# fdc.net
KiCad netlist of a schematic drawn in EAGLE
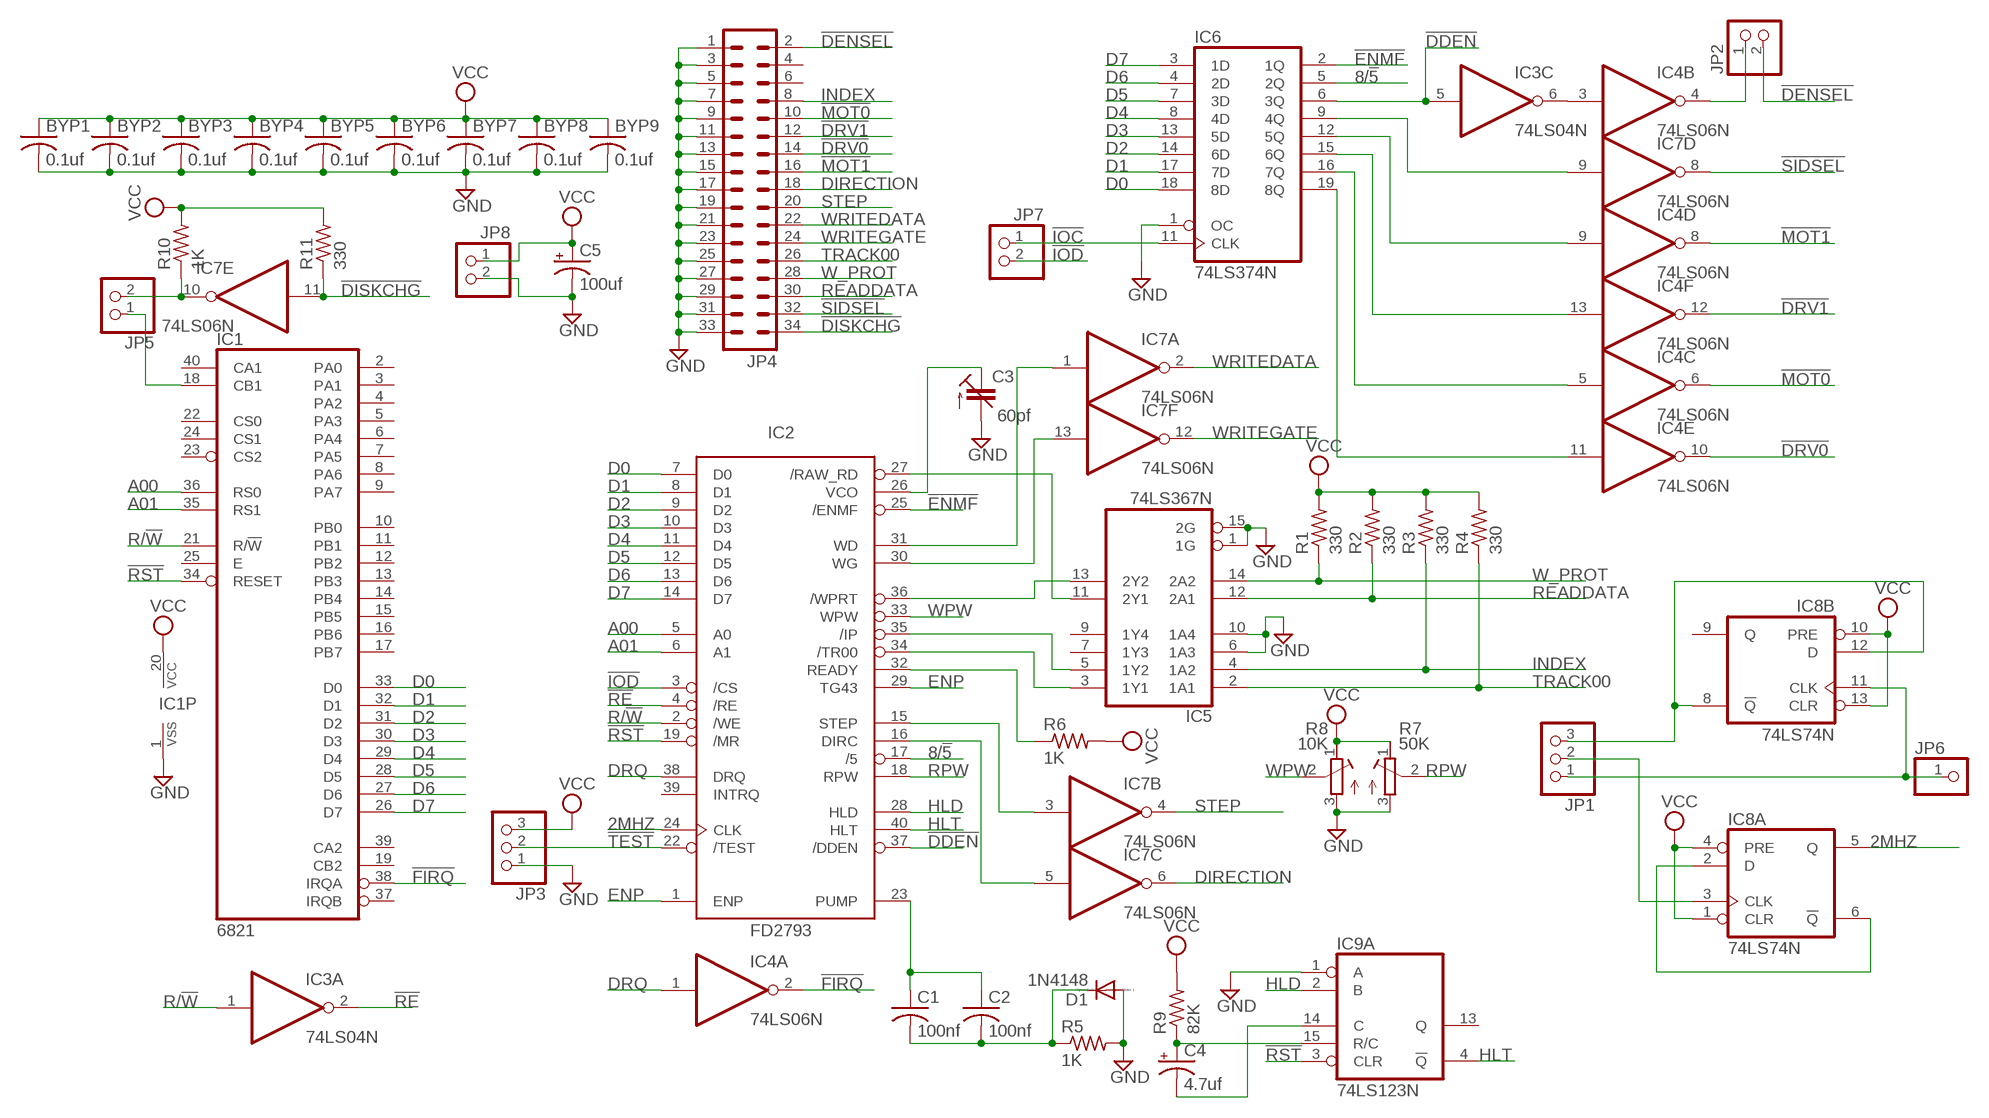
[diagram p0: schematic, sheet 1]

(export (version "E")
  (design (tool "Eeschema 10.0.6"))
  (components
    (comp (ref "BYP1")
      (value "0.1uf")
      (footprint "eagle-import:C050-025X075")
      (libsource (lib "eagle-import") (part "C-US050-025X075"))
    )
    (comp (ref "BYP2")
      (value "0.1uf")
      (footprint "eagle-import:C050-025X075")
      (libsource (lib "eagle-import") (part "C-US050-025X075"))
    )
    (comp (ref "BYP3")
      (value "0.1uf")
      (footprint "eagle-import:C050-025X075")
      (libsource (lib "eagle-import") (part "C-US050-025X075"))
    )
    (comp (ref "BYP4")
      (value "0.1uf")
      (footprint "eagle-import:C050-025X075")
      (libsource (lib "eagle-import") (part "C-US050-025X075"))
    )
    (comp (ref "BYP5")
      (value "0.1uf")
      (footprint "eagle-import:C050-025X075")
      (libsource (lib "eagle-import") (part "C-US050-025X075"))
    )
    (comp (ref "BYP6")
      (value "0.1uf")
      (footprint "eagle-import:C050-025X075")
      (libsource (lib "eagle-import") (part "C-US050-025X075"))
    )
    (comp (ref "BYP7")
      (value "0.1uf")
      (footprint "eagle-import:C050-025X075")
      (libsource (lib "eagle-import") (part "C-US050-025X075"))
    )
    (comp (ref "BYP8")
      (value "0.1uf")
      (footprint "eagle-import:C050-025X075")
      (libsource (lib "eagle-import") (part "C-US050-025X075"))
    )
    (comp (ref "BYP9")
      (value "0.1uf")
      (footprint "eagle-import:C050-025X075")
      (libsource (lib "eagle-import") (part "C-US050-025X075"))
    )
    (comp (ref "C1")
      (value "100nf")
      (footprint "eagle-import:C050-025X075")
      (libsource (lib "eagle-import") (part "C-US050-025X075"))
    )
    (comp (ref "C2")
      (value "100nf")
      (footprint "eagle-import:C050-025X075")
      (libsource (lib "eagle-import") (part "C-US050-025X075"))
    )
    (comp (ref "C3")
      (value "60pf")
      (footprint "eagle-import:CTRIM808-BC")
      (libsource (lib "eagle-import") (part "C-TRIMM808"))
    )
    (comp (ref "C4")
      (value "4.7uf")
      (footprint "eagle-import:E15-5")
      (libsource (lib "eagle-import") (part "CPOL-USE15-5AXIAL"))
    )
    (comp (ref "C5")
      (value "100uf")
      (footprint "eagle-import:E15-5")
      (libsource (lib "eagle-import") (part "CPOL-USE15-5AXIAL"))
    )
    (comp (ref "D1")
      (value "1N4148")
      (footprint "eagle-import:DO35-10")
      (libsource (lib "eagle-import") (part "1N4148DO35-10"))
    )
    (comp (ref "IC1")
      (value "6821")
      (footprint "eagle-import:DIL40")
      (fields (field (name "MF") "NTE ELECTRONICS") (field (name "MPN") "NTE6821"))
      (libsource (lib "eagle-import") (part "6821"))
    )
    (comp (ref "IC2")
      (value "FD2793")
      (footprint "eagle-import:DIL40")
      (libsource (lib "eagle-import") (part "FD2793"))
    )
    (comp (ref "IC3")
      (value "74LS04N")
      (footprint "eagle-import:DIL14")
      (libsource (lib "eagle-import") (part "7404NLS"))
    )
    (comp (ref "IC4")
      (value "74LS06N")
      (footprint "eagle-import:DIL14")
      (libsource (lib "eagle-import") (part "7406NLS"))
    )
    (comp (ref "IC5")
      (value "74LS367N")
      (footprint "eagle-import:DIL16")
      (libsource (lib "eagle-import") (part "74367N"))
    )
    (comp (ref "IC6")
      (value "74LS374N")
      (footprint "eagle-import:DIL20")
      (libsource (lib "eagle-import") (part "74374NLS"))
    )
    (comp (ref "IC7")
      (value "74LS06N")
      (footprint "eagle-import:DIL14")
      (libsource (lib "eagle-import") (part "7406NLS"))
    )
    (comp (ref "IC8")
      (value "74LS74N")
      (footprint "eagle-import:DIL14")
      (libsource (lib "eagle-import") (part "7474NLS"))
    )
    (comp (ref "IC9")
      (value "74LS123N")
      (footprint "eagle-import:DIL16")
      (libsource (lib "eagle-import") (part "74123NLS"))
    )
    (comp (ref "JP1")
      (value "PINHD-1X3")
      (footprint "eagle-import:1X03")
      (libsource (lib "eagle-import") (part "PINHD-1X3"))
    )
    (comp (ref "JP2")
      (value "PINHD-1X2")
      (footprint "eagle-import:1X02")
      (libsource (lib "eagle-import") (part "PINHD-1X2"))
    )
    (comp (ref "JP3")
      (value "PINHD-1X3")
      (footprint "eagle-import:1X03")
      (libsource (lib "eagle-import") (part "PINHD-1X3"))
    )
    (comp (ref "JP4")
      (value "MA17-2")
      (footprint "eagle-import:MA17-2")
      (libsource (lib "eagle-import") (part "MA17-2"))
    )
    (comp (ref "JP5")
      (value "PINHD-1X2")
      (footprint "eagle-import:1X02")
      (libsource (lib "eagle-import") (part "PINHD-1X2"))
    )
    (comp (ref "JP6")
      (value "PINHD-1X1")
      (footprint "eagle-import:1X01")
      (libsource (lib "eagle-import") (part "PINHD-1X1"))
    )
    (comp (ref "JP7")
      (value "PINHD-1X2")
      (footprint "eagle-import:1X02")
      (libsource (lib "eagle-import") (part "PINHD-1X2"))
    )
    (comp (ref "JP8")
      (value "PINHD-1X2")
      (footprint "eagle-import:1X02")
      (libsource (lib "eagle-import") (part "PINHD-1X2"))
    )
    (comp (ref "R1")
      (value "330")
      (footprint "eagle-import:0207_10")
      (libsource (lib "eagle-import") (part "R-US_0207/10"))
    )
    (comp (ref "R2")
      (value "330")
      (footprint "eagle-import:0207_10")
      (libsource (lib "eagle-import") (part "R-US_0207/10"))
    )
    (comp (ref "R3")
      (value "330")
      (footprint "eagle-import:0207_10")
      (libsource (lib "eagle-import") (part "R-US_0207/10"))
    )
    (comp (ref "R4")
      (value "330")
      (footprint "eagle-import:0207_10")
      (libsource (lib "eagle-import") (part "R-US_0207/10"))
    )
    (comp (ref "R5")
      (value "1K")
      (footprint "eagle-import:0207_10")
      (libsource (lib "eagle-import") (part "R-US_0207/10"))
    )
    (comp (ref "R6")
      (value "1K")
      (footprint "eagle-import:0207_10")
      (libsource (lib "eagle-import") (part "R-US_0207/10"))
    )
    (comp (ref "R7")
      (value "50K")
      (footprint "eagle-import:RTRIM43P")
      (libsource (lib "eagle-import") (part "R-TRIMM43P"))
    )
    (comp (ref "R8")
      (value "10K")
      (footprint "eagle-import:RTRIM43P")
      (libsource (lib "eagle-import") (part "R-TRIMM43P"))
    )
    (comp (ref "R9")
      (value "82K")
      (footprint "eagle-import:0207_10")
      (libsource (lib "eagle-import") (part "R-US_0207/10"))
    )
    (comp (ref "R10")
      (value "1K")
      (footprint "eagle-import:0207_10")
      (libsource (lib "eagle-import") (part "R-US_0207/10"))
    )
    (comp (ref "R11")
      (value "330")
      (footprint "eagle-import:0207_10")
      (libsource (lib "eagle-import") (part "R-US_0207/10"))
    )
  )
  (nets
    (net (code "1") (name "/2MHZ") (class "Default")
      (node (ref "IC2") (pin "24") (pinfunction "CLK_24") (pintype "input"))
      (node (ref "IC8") (pin "5") (pinfunction "Q_5") (pintype "output"))
    )
    (net (code "2") (name "/8{slash}~{5}") (class "Default")
      (node (ref "IC2") (pin "17") (pinfunction "/5_17") (pintype "output"))
      (node (ref "IC6") (pin "5") (pinfunction "2Q_5") (pintype "tri_state"))
    )
    (net (code "3") (name "/A00") (class "Default")
      (node (ref "IC1") (pin "36") (pinfunction "RS0_36") (pintype "input"))
      (node (ref "IC2") (pin "5") (pinfunction "A0_5") (pintype "input"))
    )
    (net (code "4") (name "/A01") (class "Default")
      (node (ref "IC1") (pin "35") (pinfunction "RS1_35") (pintype "input"))
      (node (ref "IC2") (pin "6") (pinfunction "A1_6") (pintype "input"))
    )
    (net (code "5") (name "/D0") (class "Default")
      (node (ref "IC1") (pin "33") (pinfunction "D0_33") (pintype "bidirectional"))
      (node (ref "IC2") (pin "7") (pinfunction "D0_7") (pintype "bidirectional"))
      (node (ref "IC6") (pin "18") (pinfunction "8D_18") (pintype "input"))
    )
    (net (code "6") (name "/D1") (class "Default")
      (node (ref "IC1") (pin "32") (pinfunction "D1_32") (pintype "bidirectional"))
      (node (ref "IC2") (pin "8") (pinfunction "D1_8") (pintype "bidirectional"))
      (node (ref "IC6") (pin "17") (pinfunction "7D_17") (pintype "input"))
    )
    (net (code "7") (name "/D2") (class "Default")
      (node (ref "IC1") (pin "31") (pinfunction "D2_31") (pintype "bidirectional"))
      (node (ref "IC2") (pin "9") (pinfunction "D2_9") (pintype "bidirectional"))
      (node (ref "IC6") (pin "14") (pinfunction "6D_14") (pintype "input"))
    )
    (net (code "8") (name "/D3") (class "Default")
      (node (ref "IC1") (pin "30") (pinfunction "D3_30") (pintype "bidirectional"))
      (node (ref "IC2") (pin "10") (pinfunction "D3_10") (pintype "bidirectional"))
      (node (ref "IC6") (pin "13") (pinfunction "5D_13") (pintype "input"))
    )
    (net (code "9") (name "/D4") (class "Default")
      (node (ref "IC1") (pin "29") (pinfunction "D4_29") (pintype "bidirectional"))
      (node (ref "IC2") (pin "11") (pinfunction "D4_11") (pintype "bidirectional"))
      (node (ref "IC6") (pin "8") (pinfunction "4D_8") (pintype "input"))
    )
    (net (code "10") (name "/D5") (class "Default")
      (node (ref "IC1") (pin "28") (pinfunction "D5_28") (pintype "bidirectional"))
      (node (ref "IC2") (pin "12") (pinfunction "D5_12") (pintype "bidirectional"))
      (node (ref "IC6") (pin "7") (pinfunction "3D_7") (pintype "input"))
    )
    (net (code "11") (name "/D6") (class "Default")
      (node (ref "IC1") (pin "27") (pinfunction "D6_27") (pintype "bidirectional"))
      (node (ref "IC2") (pin "13") (pinfunction "D6_13") (pintype "bidirectional"))
      (node (ref "IC6") (pin "4") (pinfunction "2D_4") (pintype "input"))
    )
    (net (code "12") (name "/D7") (class "Default")
      (node (ref "IC1") (pin "26") (pinfunction "D7_26") (pintype "bidirectional"))
      (node (ref "IC2") (pin "14") (pinfunction "D7_14") (pintype "bidirectional"))
      (node (ref "IC6") (pin "3") (pinfunction "1D_3") (pintype "input"))
    )
    (net (code "13") (name "/DIRECTION") (class "Default")
      (node (ref "IC7") (pin "6") (pinfunction "O_6") (pintype "open_collector"))
      (node (ref "JP4") (pin "18") (pinfunction "18_18") (pintype "passive"))
    )
    (net (code "14") (name "/DRQ") (class "Default")
      (node (ref "IC2") (pin "38") (pinfunction "DRQ_38") (pintype "output"))
      (node (ref "IC4") (pin "1") (pinfunction "I_1") (pintype "input"))
    )
    (net (code "15") (name "/ENP") (class "Default")
      (node (ref "IC2") (pin "1") (pinfunction "ENP_1") (pintype "power_in"))
      (node (ref "IC2") (pin "29") (pinfunction "TG43_29") (pintype "output"))
    )
    (net (code "16") (name "/HLD") (class "Default")
      (node (ref "IC2") (pin "28") (pinfunction "HLD_28") (pintype "output"))
      (node (ref "IC9") (pin "2") (pinfunction "B_2") (pintype "input"))
    )
    (net (code "17") (name "/HLT") (class "Default")
      (node (ref "IC2") (pin "40") (pinfunction "HLT_40") (pintype "input"))
      (node (ref "IC9") (pin "4") (pinfunction "~{Q}_4") (pintype "output"))
    )
    (net (code "18") (name "/INDEX") (class "Default")
      (node (ref "IC5") (pin "4") (pinfunction "1A2_4") (pintype "input"))
      (node (ref "JP4") (pin "8") (pinfunction "8_8") (pintype "passive"))
      (node (ref "R3") (pin "1") (pinfunction "1_1") (pintype "passive"))
    )
    (net (code "19") (name "/READDATA") (class "Default")
      (node (ref "IC5") (pin "12") (pinfunction "2A1_12") (pintype "input"))
      (node (ref "JP4") (pin "30") (pinfunction "30_30") (pintype "passive"))
      (node (ref "R2") (pin "1") (pinfunction "1_1") (pintype "passive"))
    )
    (net (code "20") (name "/RPW") (class "Default")
      (node (ref "IC2") (pin "18") (pinfunction "RPW_18") (pintype "input"))
      (node (ref "R7") (pin "2") (pinfunction "S_2") (pintype "passive"))
    )
    (net (code "21") (name "/R{slash}~{W}") (class "Default")
      (node (ref "IC1") (pin "21") (pinfunction "R/~{W}_21") (pintype "input"))
      (node (ref "IC2") (pin "2") (pinfunction "/WE_2") (pintype "input"))
      (node (ref "IC3") (pin "1") (pinfunction "I_1") (pintype "input"))
    )
    (net (code "22") (name "/STEP") (class "Default")
      (node (ref "IC7") (pin "4") (pinfunction "O_4") (pintype "open_collector"))
      (node (ref "JP4") (pin "20") (pinfunction "20_20") (pintype "passive"))
    )
    (net (code "23") (name "/TRACK00") (class "Default")
      (node (ref "IC5") (pin "2") (pinfunction "1A1_2") (pintype "input"))
      (node (ref "JP4") (pin "26") (pinfunction "26_26") (pintype "passive"))
      (node (ref "R4") (pin "1") (pinfunction "1_1") (pintype "passive"))
    )
    (net (code "24") (name "/WPW") (class "Default")
      (node (ref "IC2") (pin "33") (pinfunction "WPW_33") (pintype "input"))
      (node (ref "R8") (pin "2") (pinfunction "S_2") (pintype "passive"))
    )
    (net (code "25") (name "/WRITEDATA") (class "Default")
      (node (ref "IC7") (pin "2") (pinfunction "O_2") (pintype "open_collector"))
      (node (ref "JP4") (pin "22") (pinfunction "22_22") (pintype "passive"))
    )
    (net (code "26") (name "/WRITEGATE") (class "Default")
      (node (ref "IC7") (pin "12") (pinfunction "O_12") (pintype "open_collector"))
      (node (ref "JP4") (pin "24") (pinfunction "24_24") (pintype "passive"))
    )
    (net (code "27") (name "/W_PROT") (class "Default")
      (node (ref "IC5") (pin "14") (pinfunction "2A2_14") (pintype "input"))
      (node (ref "JP4") (pin "28") (pinfunction "28_28") (pintype "passive"))
      (node (ref "R1") (pin "1") (pinfunction "1_1") (pintype "passive"))
    )
    (net (code "28") (name "/~{DDEN}") (class "Default")
      (node (ref "IC2") (pin "37") (pinfunction "/DDEN_37") (pintype "input"))
      (node (ref "IC3") (pin "5") (pinfunction "I_5") (pintype "input"))
      (node (ref "IC6") (pin "6") (pinfunction "3Q_6") (pintype "tri_state"))
    )
    (net (code "29") (name "/~{DENSEL}") (class "Default")
      (node (ref "JP2") (pin "2") (pinfunction "2_2") (pintype "passive"))
      (node (ref "JP4") (pin "2") (pinfunction "2_2") (pintype "passive"))
    )
    (net (code "30") (name "/~{DISKCHG}") (class "Default")
      (node (ref "IC7") (pin "11") (pinfunction "I_11") (pintype "input"))
      (node (ref "JP4") (pin "34") (pinfunction "34_34") (pintype "passive"))
      (node (ref "R11") (pin "1") (pinfunction "1_1") (pintype "passive"))
    )
    (net (code "31") (name "/~{DRV0}") (class "Default")
      (node (ref "IC4") (pin "10") (pinfunction "O_10") (pintype "open_collector"))
      (node (ref "JP4") (pin "14") (pinfunction "14_14") (pintype "passive"))
    )
    (net (code "32") (name "/~{DRV1}") (class "Default")
      (node (ref "IC4") (pin "12") (pinfunction "O_12") (pintype "open_collector"))
      (node (ref "JP4") (pin "12") (pinfunction "12_12") (pintype "passive"))
    )
    (net (code "33") (name "/~{ENMF}") (class "Default")
      (node (ref "IC2") (pin "25") (pinfunction "/ENMF_25") (pintype "input"))
      (node (ref "IC6") (pin "2") (pinfunction "1Q_2") (pintype "tri_state"))
    )
    (net (code "34") (name "/~{FIRQ}") (class "Default")
      (node (ref "IC1") (pin "38") (pinfunction "IRQA_38") (pintype "open_collector"))
      (node (ref "IC4") (pin "2") (pinfunction "O_2") (pintype "open_collector"))
    )
    (net (code "35") (name "/~{IOC}") (class "Default")
      (node (ref "IC6") (pin "11") (pinfunction "CLK_11") (pintype "input"))
      (node (ref "JP7") (pin "1") (pinfunction "1_1") (pintype "passive"))
    )
    (net (code "36") (name "/~{IOD}") (class "Default")
      (node (ref "IC2") (pin "3") (pinfunction "/CS_3") (pintype "input"))
      (node (ref "JP7") (pin "2") (pinfunction "2_2") (pintype "passive"))
    )
    (net (code "37") (name "/~{MOT0}") (class "Default")
      (node (ref "IC4") (pin "6") (pinfunction "O_6") (pintype "open_collector"))
      (node (ref "JP4") (pin "10") (pinfunction "10_10") (pintype "passive"))
    )
    (net (code "38") (name "/~{MOT1}") (class "Default")
      (node (ref "IC4") (pin "8") (pinfunction "O_8") (pintype "open_collector"))
      (node (ref "JP4") (pin "16") (pinfunction "16_16") (pintype "passive"))
    )
    (net (code "39") (name "/~{RE}") (class "Default")
      (node (ref "IC2") (pin "4") (pinfunction "/RE_4") (pintype "input"))
      (node (ref "IC3") (pin "2") (pinfunction "O_2") (pintype "output"))
    )
    (net (code "40") (name "/~{RST}") (class "Default")
      (node (ref "IC1") (pin "34") (pinfunction "RESET_34") (pintype "input"))
      (node (ref "IC2") (pin "19") (pinfunction "/MR_19") (pintype "input"))
      (node (ref "IC9") (pin "3") (pinfunction "CLR_3") (pintype "input"))
    )
    (net (code "41") (name "/~{SIDSEL}") (class "Default")
      (node (ref "IC7") (pin "8") (pinfunction "O_8") (pintype "open_collector"))
      (node (ref "JP4") (pin "32") (pinfunction "32_32") (pintype "passive"))
    )
    (net (code "42") (name "/~{TEST}") (class "Default")
      (node (ref "IC2") (pin "22") (pinfunction "/TEST_22") (pintype "input"))
      (node (ref "JP3") (pin "2") (pinfunction "2_2") (pintype "passive"))
    )
    (net (code "43") (name "GND") (class "Default")
      (node (ref "BYP1") (pin "2") (pinfunction "2_2") (pintype "passive"))
      (node (ref "BYP2") (pin "2") (pinfunction "2_2") (pintype "passive"))
      (node (ref "BYP3") (pin "2") (pinfunction "2_2") (pintype "passive"))
      (node (ref "BYP4") (pin "2") (pinfunction "2_2") (pintype "passive"))
      (node (ref "BYP5") (pin "2") (pinfunction "2_2") (pintype "passive"))
      (node (ref "BYP6") (pin "2") (pinfunction "2_2") (pintype "passive"))
      (node (ref "BYP7") (pin "2") (pinfunction "2_2") (pintype "passive"))
      (node (ref "BYP8") (pin "2") (pinfunction "2_2") (pintype "passive"))
      (node (ref "BYP9") (pin "2") (pinfunction "2_2") (pintype "passive"))
      (node (ref "C3") (pin "2") (pinfunction "A_2") (pintype "passive"))
      (node (ref "C5") (pin "-") (pinfunction "-_-") (pintype "passive"))
      (node (ref "D1") (pin "A") (pinfunction "A_A") (pintype "passive"))
      (node (ref "IC1") (pin "1") (pinfunction "VSS_1") (pintype "power_in"))
      (node (ref "IC5") (pin "1") (pinfunction "1G_1") (pintype "input"))
      (node (ref "IC5") (pin "10") (pinfunction "1A4_10") (pintype "input"))
      (node (ref "IC5") (pin "15") (pinfunction "2G_15") (pintype "input"))
      (node (ref "IC5") (pin "6") (pinfunction "1A3_6") (pintype "input"))
      (node (ref "IC6") (pin "1") (pinfunction "OC_1") (pintype "input"))
      (node (ref "IC9") (pin "1") (pinfunction "A_1") (pintype "input"))
      (node (ref "JP3") (pin "1") (pinfunction "1_1") (pintype "passive"))
      (node (ref "JP4") (pin "1") (pinfunction "1_1") (pintype "passive"))
      (node (ref "JP4") (pin "11") (pinfunction "11_11") (pintype "passive"))
      (node (ref "JP4") (pin "13") (pinfunction "13_13") (pintype "passive"))
      (node (ref "JP4") (pin "15") (pinfunction "15_15") (pintype "passive"))
      (node (ref "JP4") (pin "17") (pinfunction "17_17") (pintype "passive"))
      (node (ref "JP4") (pin "19") (pinfunction "19_19") (pintype "passive"))
      (node (ref "JP4") (pin "21") (pinfunction "21_21") (pintype "passive"))
      (node (ref "JP4") (pin "23") (pinfunction "23_23") (pintype "passive"))
      (node (ref "JP4") (pin "25") (pinfunction "25_25") (pintype "passive"))
      (node (ref "JP4") (pin "27") (pinfunction "27_27") (pintype "passive"))
      (node (ref "JP4") (pin "29") (pinfunction "29_29") (pintype "passive"))
      (node (ref "JP4") (pin "3") (pinfunction "3_3") (pintype "passive"))
      (node (ref "JP4") (pin "31") (pinfunction "31_31") (pintype "passive"))
      (node (ref "JP4") (pin "33") (pinfunction "33_33") (pintype "passive"))
      (node (ref "JP4") (pin "5") (pinfunction "5_5") (pintype "passive"))
      (node (ref "JP4") (pin "7") (pinfunction "7_7") (pintype "passive"))
      (node (ref "JP4") (pin "9") (pinfunction "9_9") (pintype "passive"))
      (node (ref "JP8") (pin "2") (pinfunction "2_2") (pintype "passive"))
      (node (ref "R5") (pin "2") (pinfunction "2_2") (pintype "passive"))
      (node (ref "R7") (pin "3") (pinfunction "A_3") (pintype "passive"))
      (node (ref "R8") (pin "3") (pinfunction "A_3") (pintype "passive"))
    )
    (net (code "44") (name "Net-(C1-Pad2)") (class "Default")
      (node (ref "C1") (pin "2") (pinfunction "2_2") (pintype "passive"))
      (node (ref "C2") (pin "2") (pinfunction "2_2") (pintype "passive"))
      (node (ref "D1") (pin "C") (pinfunction "C_C") (pintype "passive"))
      (node (ref "R5") (pin "1") (pinfunction "1_1") (pintype "passive"))
    )
    (net (code "45") (name "Net-(C3-E)") (class "Default")
      (node (ref "C3") (pin "1") (pinfunction "E_1") (pintype "passive"))
      (node (ref "IC2") (pin "26") (pinfunction "VCO_26") (pintype "input"))
    )
    (net (code "46") (name "Net-(IC1A-CB1)") (class "Default")
      (node (ref "IC1") (pin "18") (pinfunction "CB1_18") (pintype "input"))
      (node (ref "JP5") (pin "1") (pinfunction "1_1") (pintype "passive"))
    )
    (net (code "47") (name "Net-(IC2A-DIRC)") (class "Default")
      (node (ref "IC2") (pin "16") (pinfunction "DIRC_16") (pintype "output"))
      (node (ref "IC7") (pin "5") (pinfunction "I_5") (pintype "input"))
    )
    (net (code "48") (name "Net-(IC2A-PUMP)") (class "Default")
      (node (ref "C1") (pin "1") (pinfunction "1_1") (pintype "passive"))
      (node (ref "C2") (pin "1") (pinfunction "1_1") (pintype "passive"))
      (node (ref "IC2") (pin "23") (pinfunction "PUMP_23") (pintype "power_in"))
    )
    (net (code "49") (name "Net-(IC2A-READY)") (class "Default")
      (node (ref "IC2") (pin "32") (pinfunction "READY_32") (pintype "input"))
      (node (ref "R6") (pin "1") (pinfunction "1_1") (pintype "passive"))
    )
    (net (code "50") (name "Net-(IC2A-STEP)") (class "Default")
      (node (ref "IC2") (pin "15") (pinfunction "STEP_15") (pintype "output"))
      (node (ref "IC7") (pin "3") (pinfunction "I_3") (pintype "input"))
    )
    (net (code "51") (name "Net-(IC2A-WD)") (class "Default")
      (node (ref "IC2") (pin "31") (pinfunction "WD_31") (pintype "output"))
      (node (ref "IC7") (pin "1") (pinfunction "I_1") (pintype "input"))
    )
    (net (code "52") (name "Net-(IC2A-WG)") (class "Default")
      (node (ref "IC2") (pin "30") (pinfunction "WG_30") (pintype "output"))
      (node (ref "IC7") (pin "13") (pinfunction "I_13") (pintype "input"))
    )
    (net (code "53") (name "Net-(IC2A-{slash}IP)") (class "Default")
      (node (ref "IC2") (pin "35") (pinfunction "/IP_35") (pintype "input"))
      (node (ref "IC5") (pin "5") (pinfunction "1Y2_5") (pintype "tri_state"))
    )
    (net (code "54") (name "Net-(IC2A-{slash}RAW_RD)") (class "Default")
      (node (ref "IC2") (pin "27") (pinfunction "/RAW_RD_27") (pintype "input"))
      (node (ref "IC5") (pin "11") (pinfunction "2Y1_11") (pintype "tri_state"))
    )
    (net (code "55") (name "Net-(IC2A-{slash}TR00)") (class "Default")
      (node (ref "IC2") (pin "34") (pinfunction "/TR00_34") (pintype "input"))
      (node (ref "IC5") (pin "3") (pinfunction "1Y1_3") (pintype "tri_state"))
    )
    (net (code "56") (name "Net-(IC2A-{slash}WPRT)") (class "Default")
      (node (ref "IC2") (pin "36") (pinfunction "/WPRT_36") (pintype "input"))
      (node (ref "IC5") (pin "13") (pinfunction "2Y2_13") (pintype "tri_state"))
    )
    (net (code "57") (name "Net-(IC3C-O)") (class "Default")
      (node (ref "IC3") (pin "6") (pinfunction "O_6") (pintype "output"))
      (node (ref "IC4") (pin "3") (pinfunction "I_3") (pintype "input"))
    )
    (net (code "58") (name "Net-(IC4B-O)") (class "Default")
      (node (ref "IC4") (pin "4") (pinfunction "O_4") (pintype "open_collector"))
      (node (ref "JP2") (pin "1") (pinfunction "1_1") (pintype "passive"))
    )
    (net (code "59") (name "Net-(IC4C-I)") (class "Default")
      (node (ref "IC4") (pin "5") (pinfunction "I_5") (pintype "input"))
      (node (ref "IC6") (pin "16") (pinfunction "7Q_16") (pintype "tri_state"))
    )
    (net (code "60") (name "Net-(IC4D-I)") (class "Default")
      (node (ref "IC4") (pin "9") (pinfunction "I_9") (pintype "input"))
      (node (ref "IC6") (pin "12") (pinfunction "5Q_12") (pintype "tri_state"))
    )
    (net (code "61") (name "Net-(IC4E-I)") (class "Default")
      (node (ref "IC4") (pin "11") (pinfunction "I_11") (pintype "input"))
      (node (ref "IC6") (pin "19") (pinfunction "8Q_19") (pintype "tri_state"))
    )
    (net (code "62") (name "Net-(IC4F-I)") (class "Default")
      (node (ref "IC4") (pin "13") (pinfunction "I_13") (pintype "input"))
      (node (ref "IC6") (pin "15") (pinfunction "6Q_15") (pintype "tri_state"))
    )
    (net (code "63") (name "Net-(IC6A-4Q)") (class "Default")
      (node (ref "IC6") (pin "9") (pinfunction "4Q_9") (pintype "tri_state"))
      (node (ref "IC7") (pin "9") (pinfunction "I_9") (pintype "input"))
    )
    (net (code "64") (name "Net-(IC7E-O)") (class "Default")
      (node (ref "IC7") (pin "10") (pinfunction "O_10") (pintype "open_collector"))
      (node (ref "JP5") (pin "2") (pinfunction "2_2") (pintype "passive"))
      (node (ref "R10") (pin "1") (pinfunction "1_1") (pintype "passive"))
    )
    (net (code "65") (name "Net-(IC8A-CLK)") (class "Default")
      (node (ref "IC8") (pin "3") (pinfunction "CLK_3") (pintype "input"))
      (node (ref "JP1") (pin "2") (pinfunction "2_2") (pintype "passive"))
    )
    (net (code "66") (name "Net-(IC8A-D)") (class "Default")
      (node (ref "IC8") (pin "2") (pinfunction "D_2") (pintype "input"))
      (node (ref "IC8") (pin "6") (pinfunction "~{Q}_6") (pintype "output"))
    )
    (net (code "67") (name "Net-(IC8B-CLK)") (class "Default")
      (node (ref "IC8") (pin "11") (pinfunction "CLK_11") (pintype "input"))
      (node (ref "JP1") (pin "1") (pinfunction "1_1") (pintype "passive"))
      (node (ref "JP6") (pin "1") (pinfunction "1_1") (pintype "passive"))
    )
    (net (code "68") (name "Net-(IC8B-D)") (class "Default")
      (node (ref "IC8") (pin "12") (pinfunction "D_12") (pintype "input"))
      (node (ref "IC8") (pin "8") (pinfunction "~{Q}_8") (pintype "output"))
      (node (ref "JP1") (pin "3") (pinfunction "3_3") (pintype "passive"))
    )
    (net (code "69") (name "Net-(IC9A-C)") (class "Default")
      (node (ref "C4") (pin "-") (pinfunction "-_-") (pintype "passive"))
      (node (ref "IC9") (pin "14") (pinfunction "C_14") (pintype "input"))
    )
    (net (code "70") (name "Net-(IC9A-R{slash}C)") (class "Default")
      (node (ref "C4") (pin "+") (pinfunction "+_+") (pintype "passive"))
      (node (ref "IC9") (pin "15") (pinfunction "R/C_15") (pintype "input"))
      (node (ref "R9") (pin "1") (pinfunction "1_1") (pintype "passive"))
    )
    (net (code "71") (name "VCC") (class "Default")
      (node (ref "BYP1") (pin "1") (pinfunction "1_1") (pintype "passive"))
      (node (ref "BYP2") (pin "1") (pinfunction "1_1") (pintype "passive"))
      (node (ref "BYP3") (pin "1") (pinfunction "1_1") (pintype "passive"))
      (node (ref "BYP4") (pin "1") (pinfunction "1_1") (pintype "passive"))
      (node (ref "BYP5") (pin "1") (pinfunction "1_1") (pintype "passive"))
      (node (ref "BYP6") (pin "1") (pinfunction "1_1") (pintype "passive"))
      (node (ref "BYP7") (pin "1") (pinfunction "1_1") (pintype "passive"))
      (node (ref "BYP8") (pin "1") (pinfunction "1_1") (pintype "passive"))
      (node (ref "BYP9") (pin "1") (pinfunction "1_1") (pintype "passive"))
      (node (ref "C5") (pin "+") (pinfunction "+_+") (pintype "passive"))
      (node (ref "IC1") (pin "20") (pinfunction "VCC_20") (pintype "power_in"))
      (node (ref "IC8") (pin "1") (pinfunction "CLR_1") (pintype "input"))
      (node (ref "IC8") (pin "10") (pinfunction "PRE_10") (pintype "input"))
      (node (ref "IC8") (pin "13") (pinfunction "CLR_13") (pintype "input"))
      (node (ref "IC8") (pin "4") (pinfunction "PRE_4") (pintype "input"))
      (node (ref "JP3") (pin "3") (pinfunction "3_3") (pintype "passive"))
      (node (ref "JP8") (pin "1") (pinfunction "1_1") (pintype "passive"))
      (node (ref "R1") (pin "2") (pinfunction "2_2") (pintype "passive"))
      (node (ref "R10") (pin "2") (pinfunction "2_2") (pintype "passive"))
      (node (ref "R11") (pin "2") (pinfunction "2_2") (pintype "passive"))
      (node (ref "R2") (pin "2") (pinfunction "2_2") (pintype "passive"))
      (node (ref "R3") (pin "2") (pinfunction "2_2") (pintype "passive"))
      (node (ref "R4") (pin "2") (pinfunction "2_2") (pintype "passive"))
      (node (ref "R6") (pin "2") (pinfunction "2_2") (pintype "passive"))
      (node (ref "R7") (pin "1") (pinfunction "E_1") (pintype "passive"))
      (node (ref "R8") (pin "1") (pinfunction "E_1") (pintype "passive"))
      (node (ref "R9") (pin "2") (pinfunction "2_2") (pintype "passive"))
    )
    (net (code "72") (name "unconnected-(IC1A-CA1-Pad40)") (class "Default")
      (node (ref "IC1") (pin "40") (pinfunction "CA1_40") (pintype "input"))
    )
    (net (code "73") (name "unconnected-(IC1A-CA2-Pad39)") (class "Default")
      (node (ref "IC1") (pin "39") (pinfunction "CA2_39") (pintype "bidirectional"))
    )
    (net (code "74") (name "unconnected-(IC1A-CB2-Pad19)") (class "Default")
      (node (ref "IC1") (pin "19") (pinfunction "CB2_19") (pintype "bidirectional"))
    )
    (net (code "75") (name "unconnected-(IC1A-CS0-Pad22)") (class "Default")
      (node (ref "IC1") (pin "22") (pinfunction "CS0_22") (pintype "input"))
    )
    (net (code "76") (name "unconnected-(IC1A-CS1-Pad24)") (class "Default")
      (node (ref "IC1") (pin "24") (pinfunction "CS1_24") (pintype "input"))
    )
    (net (code "77") (name "unconnected-(IC1A-CS2-Pad23)") (class "Default")
      (node (ref "IC1") (pin "23") (pinfunction "CS2_23") (pintype "input"))
    )
    (net (code "78") (name "unconnected-(IC1A-E-Pad25)") (class "Default")
      (node (ref "IC1") (pin "25") (pinfunction "E_25") (pintype "input"))
    )
    (net (code "79") (name "unconnected-(IC1A-IRQB-Pad37)") (class "Default")
      (node (ref "IC1") (pin "37") (pinfunction "IRQB_37") (pintype "open_collector"))
    )
    (net (code "80") (name "unconnected-(IC1A-PA0-Pad2)") (class "Default")
      (node (ref "IC1") (pin "2") (pinfunction "PA0_2") (pintype "bidirectional"))
    )
    (net (code "81") (name "unconnected-(IC1A-PA1-Pad3)") (class "Default")
      (node (ref "IC1") (pin "3") (pinfunction "PA1_3") (pintype "bidirectional"))
    )
    (net (code "82") (name "unconnected-(IC1A-PA2-Pad4)") (class "Default")
      (node (ref "IC1") (pin "4") (pinfunction "PA2_4") (pintype "bidirectional"))
    )
    (net (code "83") (name "unconnected-(IC1A-PA3-Pad5)") (class "Default")
      (node (ref "IC1") (pin "5") (pinfunction "PA3_5") (pintype "bidirectional"))
    )
    (net (code "84") (name "unconnected-(IC1A-PA4-Pad6)") (class "Default")
      (node (ref "IC1") (pin "6") (pinfunction "PA4_6") (pintype "bidirectional"))
    )
    (net (code "85") (name "unconnected-(IC1A-PA5-Pad7)") (class "Default")
      (node (ref "IC1") (pin "7") (pinfunction "PA5_7") (pintype "bidirectional"))
    )
    (net (code "86") (name "unconnected-(IC1A-PA6-Pad8)") (class "Default")
      (node (ref "IC1") (pin "8") (pinfunction "PA6_8") (pintype "bidirectional"))
    )
    (net (code "87") (name "unconnected-(IC1A-PA7-Pad9)") (class "Default")
      (node (ref "IC1") (pin "9") (pinfunction "PA7_9") (pintype "bidirectional"))
    )
    (net (code "88") (name "unconnected-(IC1A-PB0-Pad10)") (class "Default")
      (node (ref "IC1") (pin "10") (pinfunction "PB0_10") (pintype "bidirectional"))
    )
    (net (code "89") (name "unconnected-(IC1A-PB1-Pad11)") (class "Default")
      (node (ref "IC1") (pin "11") (pinfunction "PB1_11") (pintype "bidirectional"))
    )
    (net (code "90") (name "unconnected-(IC1A-PB2-Pad12)") (class "Default")
      (node (ref "IC1") (pin "12") (pinfunction "PB2_12") (pintype "bidirectional"))
    )
    (net (code "91") (name "unconnected-(IC1A-PB3-Pad13)") (class "Default")
      (node (ref "IC1") (pin "13") (pinfunction "PB3_13") (pintype "bidirectional"))
    )
    (net (code "92") (name "unconnected-(IC1A-PB4-Pad14)") (class "Default")
      (node (ref "IC1") (pin "14") (pinfunction "PB4_14") (pintype "bidirectional"))
    )
    (net (code "93") (name "unconnected-(IC1A-PB5-Pad15)") (class "Default")
      (node (ref "IC1") (pin "15") (pinfunction "PB5_15") (pintype "bidirectional"))
    )
    (net (code "94") (name "unconnected-(IC1A-PB6-Pad16)") (class "Default")
      (node (ref "IC1") (pin "16") (pinfunction "PB6_16") (pintype "bidirectional"))
    )
    (net (code "95") (name "unconnected-(IC1A-PB7-Pad17)") (class "Default")
      (node (ref "IC1") (pin "17") (pinfunction "PB7_17") (pintype "bidirectional"))
    )
    (net (code "96") (name "unconnected-(IC2A-INTRQ-Pad39)") (class "Default")
      (node (ref "IC2") (pin "39") (pinfunction "INTRQ_39") (pintype "output"))
    )
    (net (code "97") (name "unconnected-(IC5A-1Y3-Pad7)") (class "Default")
      (node (ref "IC5") (pin "7") (pinfunction "1Y3_7") (pintype "tri_state"))
    )
    (net (code "98") (name "unconnected-(IC5A-1Y4-Pad9)") (class "Default")
      (node (ref "IC5") (pin "9") (pinfunction "1Y4_9") (pintype "tri_state"))
    )
    (net (code "99") (name "unconnected-(IC8B-Q-Pad9)") (class "Default")
      (node (ref "IC8") (pin "9") (pinfunction "Q_9") (pintype "output"))
    )
    (net (code "100") (name "unconnected-(IC9A-Q-Pad13)") (class "Default")
      (node (ref "IC9") (pin "13") (pinfunction "Q_13") (pintype "output"))
    )
    (net (code "101") (name "unconnected-(JP4-Pad4)") (class "Default")
      (node (ref "JP4") (pin "4") (pinfunction "4_4") (pintype "passive"))
    )
    (net (code "102") (name "unconnected-(JP4-Pad6)") (class "Default")
      (node (ref "JP4") (pin "6") (pinfunction "6_6") (pintype "passive"))
    )
  )
)
